# H05R2x_Backend.net
KiCad netlist of a schematic drawn in Altium Designer
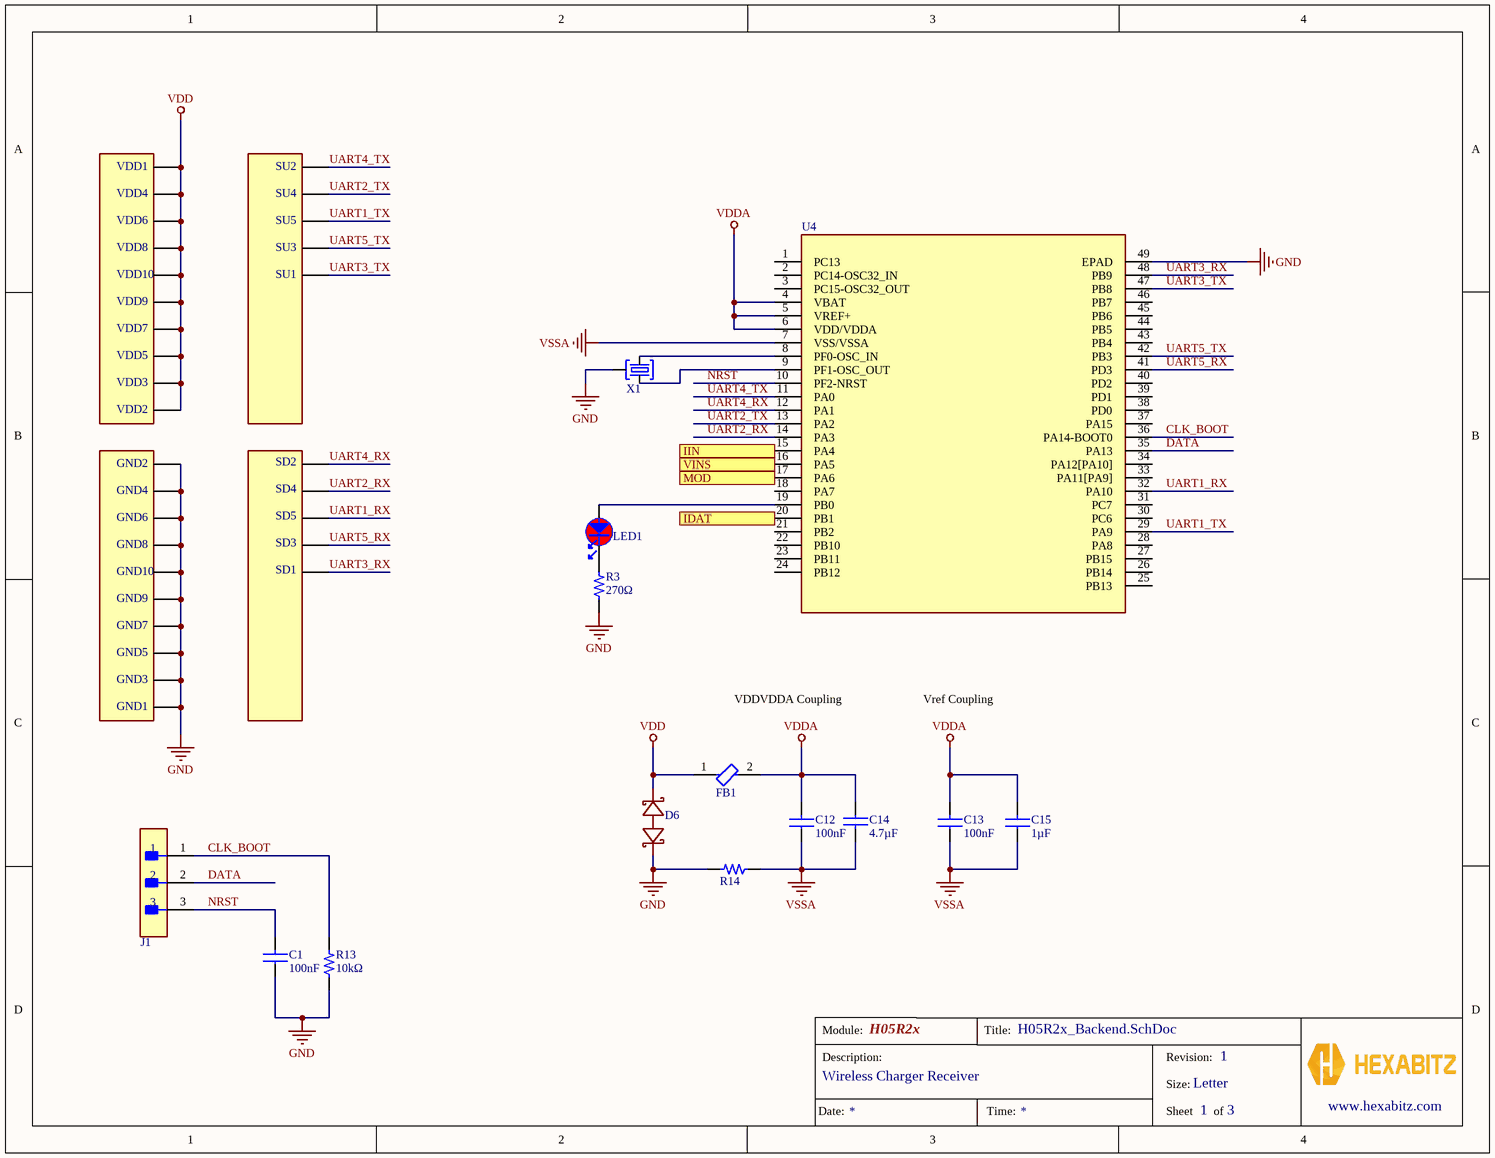
[diagram p0: H05R2x_Backend.SchDoc]

(export (version "E")
  (design (tool "Eeschema 10.0.6"))
  (components
    (comp (ref "C1")
      (value "100nF")
      (footprint "C0603")
      (fields
        (field (name "MANUFACTURER") "Samsung Electro-Mechanics")
        (field (name "MANUFACTURER PART NUMBER") "CL10B104KA8NNNC")
        (field (name "TOLERANCE") "10%")
      )
      (libsource (lib "Hexabitz Altium Library") (part "generic Capacitor"))
    )
    (comp (ref "C12")
      (value "100nF")
      (footprint "C0603")
      (fields
        (field (name "MANUFACTURER") "Samsung Electro-Mechanics")
        (field (name "MANUFACTURER PART NUMBER") "CL10B104KA8NNNC")
        (field (name "TOLERANCE") "10%")
      )
      (libsource (lib "Hexabitz Altium Library") (part "generic Capacitor"))
    )
    (comp (ref "C13")
      (value "100nF")
      (footprint "C0603")
      (fields
        (field (name "MANUFACTURER") "Samsung Electro-Mechanics")
        (field (name "MANUFACTURER PART NUMBER") "CL10B104KA8NNNC")
        (field (name "TOLERANCE") "10%")
      )
      (libsource (lib "Hexabitz Altium Library") (part "generic Capacitor"))
    )
    (comp (ref "C14")
      (value "4.7µF")
      (footprint "C0805")
      (fields
        (field (name "MANUFACTURER") "Samsung Electro-Mechanics")
        (field (name "MANUFACTURER PART NUMBER") "CL21X475KAQNNNE")
        (field (name "TOLERANCE") "10%")
      )
      (libsource (lib "Hexabitz Altium Library") (part "generic Capacitor"))
    )
    (comp (ref "C15")
      (value "1µF")
      (footprint "C0805")
      (description "Ceramic Capacitor, Ceramic, 16V, 10% +Tol, 10% -Tol, X7R, 15% TC, 1uF, Surface Mount, 0805")
      (fields
        (field (name "MANUFACTURER") "Yageo Group")
        (field (name "MANUFACTURER PART NUMBER") "CC0805KKX7R7BB105")
      )
      (libsource (lib "Hexabitz Altium Library") (part "generic Capacitor"))
    )
    (comp (ref "D6")
      (value "CDSOD323-T03SC")
      (footprint "SOD2513X114N")
      (description "A 3V, 350W, bi-directional, standard capacitance, SOD323 pkg TVS Diode ¦ Bourns CDSOD323-T03SC")
      (fields (field (name "MANUFACTURER") "Bourns"))
      (libsource (lib "Hexabitz Altium Library") (part "CDSOD323-T03SC"))
    )
    (comp (ref "FB1")
      (value "MMZ1608Y300B")
      (footprint "FP-MMZ1608-0_8-MFG")
      (description "Ferrite Beads 0603 30ohms 1500mA Signal Line AEC-Q200")
      (fields
        (field (name "MANUFACTURER") "TDK")
        (field (name "MANUFACTURER PART NUMBER") "MMZ1608Y300BTD25")
      )
      (libsource (lib "Hexabitz Altium Library") (part "MMZ1608Y300B"))
    )
    (comp (ref "GND1")
      (value "HEXABIT_UART_PORT")
      (footprint "HEXABIT_POWER_PORT_D")
      (libsource (lib "hexabitz_connectors.Library") (part "HEXABIT_POWER_PORT_D"))
    )
    (comp (ref "GND2")
      (value "HEXABIT_UART_PORT")
      (footprint "HEXABIT_POWER_PORT_D")
      (libsource (lib "hexabitz_connectors.Library") (part "HEXABIT_POWER_PORT_D"))
    )
    (comp (ref "GND3")
      (value "HEXABIT_UART_PORT")
      (footprint "HEXABIT_POWER_PORT_D")
      (libsource (lib "hexabitz_connectors.Library") (part "HEXABIT_POWER_PORT_D"))
    )
    (comp (ref "GND4")
      (value "HEXABIT_UART_PORT")
      (footprint "HEXABIT_POWER_PORT_D")
      (libsource (lib "hexabitz_connectors.Library") (part "HEXABIT_POWER_PORT_D"))
    )
    (comp (ref "GND5")
      (value "HEXABIT_UART_PORT")
      (footprint "HEXABIT_POWER_PORT_D_300L")
      (libsource (lib "hexabitz_connectors.Library") (part "HEXABIT_POWER_PORT_D_300L"))
    )
    (comp (ref "GND6")
      (value "HEXABIT_UART_PORT")
      (footprint "HEXABIT_POWER_PORT_D_300R")
      (libsource (lib "hexabitz_connectors.Library") (part "HEXABIT_POWER_PORT_D_300R"))
    )
    (comp (ref "GND7")
      (value "HEXABIT_UART_PORT")
      (footprint "HEXABIT_POWER_PORT_D")
      (libsource (lib "hexabitz_connectors.Library") (part "HEXABIT_POWER_PORT_D"))
    )
    (comp (ref "GND8")
      (value "HEXABIT_UART_PORT")
      (footprint "HEXABIT_POWER_PORT_D")
      (libsource (lib "hexabitz_connectors.Library") (part "HEXABIT_POWER_PORT_D"))
    )
    (comp (ref "GND9")
      (value "HEXABIT_UART_PORT")
      (footprint "HEXABIT_POWER_PORT_D")
      (libsource (lib "hexabitz_connectors.Library") (part "HEXABIT_POWER_PORT_D"))
    )
    (comp (ref "GND10")
      (value "HEXABIT_UART_PORT")
      (footprint "HEXABIT_POWER_PORT_D")
      (libsource (lib "hexabitz_connectors.Library") (part "HEXABIT_POWER_PORT_D"))
    )
    (comp (ref "J1")
      (value "TSW-103-14-G-S")
      (footprint "FP-TSW-103-14-G-S-MFG")
      (description "CONN HEADER VERT 3POS 2.54MM")
      (libsource (lib "Altium Content Vault") (part "cd3439d6ef35ae5d9b27ec4fdd3e828"))
    )
    (comp (ref "LED1")
      (value "VLMS1300-GS08")
      (footprint "FP-6_541-5092_01-4-MFG")
      (description "LED Uni-Color Super Red 639nm 2-Pin Chip 0603(1608Metric) T/R")
      (fields (field (name "MANUFACTURER") "Vishay Semiconductors"))
      (libsource (lib "Hexabitz Altium Library") (part "VLMS1300-GS08"))
    )
    (comp (ref "R3")
      (value "270Ω")
      (footprint "R0603")
      (description "Res Thick Film 0603 270 Ohm 5% 0.1W(1/10W) ±200ppm/C Pad SMD Automotive T/R")
      (fields
        (field (name "MANUFACTURER") "Panasonic")
        (field (name "MANUFACTURER PART NUMBER") "ERJ-3GEYJ271V")
      )
      (libsource (lib "Hexabitz Altium Library") (part "generic Resistor"))
    )
    (comp (ref "R13")
      (value "10kΩ")
      (footprint "R0603")
      (description "100mW Thick Film Resistors ±100ppm/℃ ±1% 10kΩ 0603 Chip Resistor - Surface Mount ROHS")
      (fields
        (field (name "MANUFACTURER") "Yageo Group")
        (field (name "MANUFACTURER PART NUMBER") "RC0603FR-0710KL")
      )
      (libsource (lib "") (part "generic Resistor_1"))
    )
    (comp (ref "R14")
      (value "Manufacturer Part Number")
      (footprint "R0603")
      (libsource (lib "") (part "generic Resistor_2"))
    )
    (comp (ref "SD1")
      (value "HEXABIT_UART_PORT")
      (footprint "HEXABIT_UART_PORT_D")
      (libsource (lib "hexabitz_connectors.Library") (part "HEXABIT_UART_PORT_D"))
    )
    (comp (ref "SD2")
      (value "HEXABIT_UART_PORT")
      (footprint "HEXABIT_UART_PORT_D")
      (libsource (lib "hexabitz_connectors.Library") (part "HEXABIT_UART_PORT_D"))
    )
    (comp (ref "SD3")
      (value "HEXABIT_UART_PORT")
      (footprint "HEXABIT_UART_PORT_D")
      (libsource (lib "hexabitz_connectors.Library") (part "HEXABIT_UART_PORT_D"))
    )
    (comp (ref "SD4")
      (value "HEXABIT_UART_PORT")
      (footprint "HEXABIT_UART_PORT_D")
      (libsource (lib "hexabitz_connectors.Library") (part "HEXABIT_UART_PORT_D"))
    )
    (comp (ref "SD5")
      (value "HEXABIT_UART_PORT")
      (footprint "HEXABIT_UART_PORT_D")
      (libsource (lib "hexabitz_connectors.Library") (part "HEXABIT_UART_PORT_D"))
    )
    (comp (ref "SU1")
      (value "HEXABIT_UART_PORT")
      (footprint "HEXABIT_UART_PORT_U")
      (libsource (lib "hexabitz_connectors.Library") (part "HEXABIT_UART_PORT_U"))
    )
    (comp (ref "SU2")
      (value "HEXABIT_UART_PORT")
      (footprint "HEXABIT_UART_PORT_U")
      (libsource (lib "hexabitz_connectors.Library") (part "HEXABIT_UART_PORT_U"))
    )
    (comp (ref "SU3")
      (value "HEXABIT_UART_PORT")
      (footprint "HEXABIT_UART_PORT_U")
      (libsource (lib "hexabitz_connectors.Library") (part "HEXABIT_UART_PORT_U"))
    )
    (comp (ref "SU4")
      (value "HEXABIT_UART_PORT")
      (footprint "HEXABIT_UART_PORT_U")
      (libsource (lib "hexabitz_connectors.Library") (part "HEXABIT_UART_PORT_U"))
    )
    (comp (ref "SU5")
      (value "HEXABIT_UART_PORT")
      (footprint "HEXABIT_UART_PORT_U")
      (libsource (lib "hexabitz_connectors.Library") (part "HEXABIT_UART_PORT_U"))
    )
    (comp (ref "U4")
      (value "STM32G0B1CEU6")
      (footprint "QFN50P700X700X65-49N-D")
      (description "MCU 32-bit ARM Cortex M0+ RISC 512KB Flash 1.8V/2.5V/3.3V 48-Pin UFQFPN EP Tray")
      (fields (field (name "MANUFACTURER") "STMicroelectronics"))
      (libsource (lib "Hexabitz Altium Library") (part "STM32G0B1CEU6"))
    )
    (comp (ref "VDD1")
      (value "HEXABIT_UART_PORT")
      (footprint "HEXABIT_POWER_PORT_U")
      (libsource (lib "hexabitz_connectors.Library") (part "HEXABIT_POWER_PORT_U"))
    )
    (comp (ref "VDD2")
      (value "HEXABIT_UART_PORT")
      (footprint "HEXABIT_POWER_PORT_U")
      (libsource (lib "hexabitz_connectors.Library") (part "HEXABIT_POWER_PORT_U"))
    )
    (comp (ref "VDD3")
      (value "HEXABIT_UART_PORT")
      (footprint "HEXABIT_POWER_PORT_U")
      (libsource (lib "hexabitz_connectors.Library") (part "HEXABIT_POWER_PORT_U"))
    )
    (comp (ref "VDD4")
      (value "HEXABIT_UART_PORT")
      (footprint "HEXABIT_POWER_PORT_U")
      (libsource (lib "hexabitz_connectors.Library") (part "HEXABIT_POWER_PORT_U"))
    )
    (comp (ref "VDD5")
      (value "HEXABIT_UART_PORT")
      (footprint "HEXABIT_POWER_PORT_U_300L")
      (libsource (lib "hexabitz_connectors.Library") (part "HEXABIT_POWER_PORT_U_300L"))
    )
    (comp (ref "VDD6")
      (value "HEXABIT_UART_PORT")
      (footprint "HEXABIT_POWER_PORT_U_300R")
      (libsource (lib "hexabitz_connectors.Library") (part "HEXABIT_POWER_PORT_U_300R"))
    )
    (comp (ref "VDD7")
      (value "HEXABIT_UART_PORT")
      (footprint "HEXABIT_POWER_PORT_U")
      (libsource (lib "hexabitz_connectors.Library") (part "HEXABIT_POWER_PORT_U"))
    )
    (comp (ref "VDD8")
      (value "HEXABIT_UART_PORT")
      (footprint "HEXABIT_POWER_PORT_U")
      (libsource (lib "hexabitz_connectors.Library") (part "HEXABIT_POWER_PORT_U"))
    )
    (comp (ref "VDD9")
      (value "HEXABIT_UART_PORT")
      (footprint "HEXABIT_POWER_PORT_U")
      (libsource (lib "hexabitz_connectors.Library") (part "HEXABIT_POWER_PORT_U"))
    )
    (comp (ref "VDD10")
      (value "HEXABIT_UART_PORT")
      (footprint "HEXABIT_POWER_PORT_U")
      (libsource (lib "hexabitz_connectors.Library") (part "HEXABIT_POWER_PORT_U"))
    )
    (comp (ref "X1")
      (value "CSTCE8M00G52Z-R0")
      (footprint "XTALL_CSTCE8M00G52")
      (description "Ceramic Resonator 8MHz ±0.5% (Tol) ±0.2% (Stability) 10pF 40Ohm 3-Pin CSMD T/R")
      (fields (field (name "MANUFACTURER") "Murata") (field (name "TOLERANCE") "0.5%"))
      (libsource (lib "Hexabitz Altium Library") (part "CSTCE8M00G52Z-R0"))
    )
  )
  (nets
    (net (code "1") (name "/CLK_BOOT") (class "Default")
      (node (ref "J1") (pin "1") (pinfunction "1_1") (pintype "passive"))
      (node (ref "R13") (pin "1") (pinfunction "1_1") (pintype "passive"))
      (node (ref "U4") (pin "36") (pinfunction "PA14-BOOT0_36") (pintype "passive"))
    )
    (net (code "2") (name "/DATA") (class "Default")
      (node (ref "J1") (pin "2") (pinfunction "2_2") (pintype "passive"))
      (node (ref "U4") (pin "35") (pinfunction "PA13_35") (pintype "passive"))
    )
    (net (code "3") (name "/IDAT") (class "Default")
      (node (ref "U4") (pin "20") (pinfunction "PB1_20") (pintype "passive"))
    )
    (net (code "4") (name "/IIN") (class "Default")
      (node (ref "U4") (pin "15") (pinfunction "PA4_15") (pintype "passive"))
    )
    (net (code "5") (name "/MOD") (class "Default")
      (node (ref "U4") (pin "17") (pinfunction "PA6_17") (pintype "passive"))
    )
    (net (code "6") (name "/NRST") (class "Default")
      (node (ref "C1") (pin "2") (pinfunction "2_2") (pintype "passive"))
      (node (ref "J1") (pin "3") (pinfunction "3_3") (pintype "passive"))
      (node (ref "U4") (pin "10") (pinfunction "PF2-NRST_10") (pintype "passive"))
    )
    (net (code "7") (name "/UART1_RX") (class "Default")
      (node (ref "SD5") (pin "UART_D") (pinfunction "UART_D_UART_D") (pintype "passive"))
      (node (ref "U4") (pin "32") (pinfunction "PA10_32") (pintype "passive"))
    )
    (net (code "8") (name "/UART1_TX") (class "Default")
      (node (ref "SU5") (pin "UART_U") (pinfunction "UART_U_UART_U") (pintype "passive"))
      (node (ref "U4") (pin "29") (pinfunction "PA9_29") (pintype "passive"))
    )
    (net (code "9") (name "/UART2_RX") (class "Default")
      (node (ref "SD4") (pin "UART_D") (pinfunction "UART_D_UART_D") (pintype "passive"))
      (node (ref "U4") (pin "14") (pinfunction "PA3_14") (pintype "passive"))
    )
    (net (code "10") (name "/UART2_TX") (class "Default")
      (node (ref "SU4") (pin "UART_U") (pinfunction "UART_U_UART_U") (pintype "passive"))
      (node (ref "U4") (pin "13") (pinfunction "PA2_13") (pintype "passive"))
    )
    (net (code "11") (name "/UART3_RX") (class "Default")
      (node (ref "SD1") (pin "UART_D") (pinfunction "UART_D_UART_D") (pintype "passive"))
      (node (ref "U4") (pin "48") (pinfunction "PB9_48") (pintype "passive"))
    )
    (net (code "12") (name "/UART3_TX") (class "Default")
      (node (ref "SU1") (pin "UART_U") (pinfunction "UART_U_UART_U") (pintype "passive"))
      (node (ref "U4") (pin "47") (pinfunction "PB8_47") (pintype "passive"))
    )
    (net (code "13") (name "/UART4_RX") (class "Default")
      (node (ref "SD2") (pin "UART_D") (pinfunction "UART_D_UART_D") (pintype "passive"))
      (node (ref "U4") (pin "12") (pinfunction "PA1_12") (pintype "passive"))
    )
    (net (code "14") (name "/UART4_TX") (class "Default")
      (node (ref "SU2") (pin "UART_U") (pinfunction "UART_U_UART_U") (pintype "passive"))
      (node (ref "U4") (pin "11") (pinfunction "PA0_11") (pintype "passive"))
    )
    (net (code "15") (name "/UART5_RX") (class "Default")
      (node (ref "SD3") (pin "UART_D") (pinfunction "UART_D_UART_D") (pintype "passive"))
      (node (ref "U4") (pin "41") (pinfunction "PD3_41") (pintype "passive"))
    )
    (net (code "16") (name "/UART5_TX") (class "Default")
      (node (ref "SU3") (pin "UART_U") (pinfunction "UART_U_UART_U") (pintype "passive"))
      (node (ref "U4") (pin "42") (pinfunction "PB3_42") (pintype "passive"))
    )
    (net (code "17") (name "/VINS") (class "Default")
      (node (ref "U4") (pin "16") (pinfunction "PA5_16") (pintype "passive"))
    )
    (net (code "18") (name "GND") (class "Default")
      (node (ref "C1") (pin "1") (pinfunction "1_1") (pintype "passive"))
      (node (ref "D6") (pin "1") (pinfunction "A_1") (pintype "passive"))
      (node (ref "GND1") (pin "Pwr_D") (pinfunction "Pwr_D_Pwr_D") (pintype "passive"))
      (node (ref "GND10") (pin "Pwr_D") (pinfunction "Pwr_D_Pwr_D") (pintype "passive"))
      (node (ref "GND2") (pin "Pwr_D") (pinfunction "Pwr_D_Pwr_D") (pintype "passive"))
      (node (ref "GND3") (pin "Pwr_D") (pinfunction "Pwr_D_Pwr_D") (pintype "passive"))
      (node (ref "GND4") (pin "Pwr_D") (pinfunction "Pwr_D_Pwr_D") (pintype "passive"))
      (node (ref "GND5") (pin "Pwr_D") (pinfunction "Pwr_D_Pwr_D") (pintype "passive"))
      (node (ref "GND6") (pin "Pwr_D") (pinfunction "Pwr_D_Pwr_D") (pintype "passive"))
      (node (ref "GND7") (pin "Pwr_D") (pinfunction "Pwr_D_Pwr_D") (pintype "passive"))
      (node (ref "GND8") (pin "Pwr_D") (pinfunction "Pwr_D_Pwr_D") (pintype "passive"))
      (node (ref "GND9") (pin "Pwr_D") (pinfunction "Pwr_D_Pwr_D") (pintype "passive"))
      (node (ref "R13") (pin "2") (pinfunction "2_2") (pintype "passive"))
      (node (ref "R14") (pin "1") (pinfunction "1_1") (pintype "passive"))
      (node (ref "R3") (pin "1") (pinfunction "1_1") (pintype "passive"))
      (node (ref "U4") (pin "49") (pinfunction "EPAD_49") (pintype "passive"))
      (node (ref "X1") (pin "P$2") (pinfunction "2_P$2") (pintype "passive"))
    )
    (net (code "19") (name "Net-(LED1-Pad1)") (class "Default")
      (node (ref "LED1") (pin "1") (pintype "passive"))
      (node (ref "R3") (pin "2") (pinfunction "2_2") (pintype "passive"))
    )
    (net (code "20") (name "Net-(U4-PB0)") (class "Default")
      (node (ref "LED1") (pin "2") (pintype "passive"))
      (node (ref "U4") (pin "19") (pinfunction "PB0_19") (pintype "passive"))
    )
    (net (code "21") (name "Net-(U4-PF0-OSC_IN)") (class "Default")
      (node (ref "U4") (pin "8") (pinfunction "PF0-OSC_IN_8") (pintype "passive"))
      (node (ref "X1") (pin "P$3") (pinfunction "3_P$3") (pintype "passive"))
    )
    (net (code "22") (name "Net-(U4-PF1-OSC_OUT)") (class "Default")
      (node (ref "U4") (pin "9") (pinfunction "PF1-OSC_OUT_9") (pintype "passive"))
      (node (ref "X1") (pin "P$1") (pinfunction "1_P$1") (pintype "passive"))
    )
    (net (code "23") (name "VDD") (class "Default")
      (node (ref "D6") (pin "2") (pinfunction "C_2") (pintype "passive"))
      (node (ref "FB1") (pin "1") (pinfunction "1_1") (pintype "passive"))
      (node (ref "VDD1") (pin "Pwr_U") (pinfunction "Pwr_U_Pwr_U") (pintype "passive"))
      (node (ref "VDD10") (pin "Pwr_U") (pinfunction "Pwr_U_Pwr_U") (pintype "passive"))
      (node (ref "VDD2") (pin "Pwr_U") (pinfunction "Pwr_U_Pwr_U") (pintype "passive"))
      (node (ref "VDD3") (pin "Pwr_U") (pinfunction "Pwr_U_Pwr_U") (pintype "passive"))
      (node (ref "VDD4") (pin "Pwr_U") (pinfunction "Pwr_U_Pwr_U") (pintype "passive"))
      (node (ref "VDD5") (pin "Pwr_U") (pinfunction "Pwr_U_Pwr_U") (pintype "passive"))
      (node (ref "VDD6") (pin "Pwr_U") (pinfunction "Pwr_U_Pwr_U") (pintype "passive"))
      (node (ref "VDD7") (pin "Pwr_U") (pinfunction "Pwr_U_Pwr_U") (pintype "passive"))
      (node (ref "VDD8") (pin "Pwr_U") (pinfunction "Pwr_U_Pwr_U") (pintype "passive"))
      (node (ref "VDD9") (pin "Pwr_U") (pinfunction "Pwr_U_Pwr_U") (pintype "passive"))
    )
    (net (code "24") (name "VDDA") (class "Default")
      (node (ref "C12") (pin "2") (pinfunction "2_2") (pintype "passive"))
      (node (ref "C13") (pin "2") (pinfunction "2_2") (pintype "passive"))
      (node (ref "C14") (pin "1") (pinfunction "1_1") (pintype "passive"))
      (node (ref "C15") (pin "2") (pinfunction "2_2") (pintype "passive"))
      (node (ref "FB1") (pin "2") (pinfunction "2_2") (pintype "passive"))
      (node (ref "U4") (pin "4") (pinfunction "VBAT_4") (pintype "passive"))
      (node (ref "U4") (pin "5") (pinfunction "VREF+_5") (pintype "passive"))
      (node (ref "U4") (pin "6") (pinfunction "VDD/VDDA_6") (pintype "passive"))
    )
    (net (code "25") (name "VSSA") (class "Default")
      (node (ref "C12") (pin "1") (pinfunction "1_1") (pintype "passive"))
      (node (ref "C13") (pin "1") (pinfunction "1_1") (pintype "passive"))
      (node (ref "C14") (pin "2") (pinfunction "2_2") (pintype "passive"))
      (node (ref "C15") (pin "1") (pinfunction "1_1") (pintype "passive"))
      (node (ref "R14") (pin "2") (pinfunction "2_2") (pintype "passive"))
      (node (ref "U4") (pin "7") (pinfunction "VSS/VSSA_7") (pintype "passive"))
    )
    (net (code "26") (name "unconnected-(U4-PA7-Pad18)") (class "Default")
      (node (ref "U4") (pin "18") (pinfunction "PA7_18") (pintype "passive"))
    )
    (net (code "27") (name "unconnected-(U4-PA8-Pad28)") (class "Default")
      (node (ref "U4") (pin "28") (pinfunction "PA8_28") (pintype "passive"))
    )
    (net (code "28") (name "unconnected-(U4-PA11[PA9]-Pad33)") (class "Default")
      (node (ref "U4") (pin "33") (pinfunction "PA11[PA9]_33") (pintype "passive"))
    )
    (net (code "29") (name "unconnected-(U4-PA12[PA10]-Pad34)") (class "Default")
      (node (ref "U4") (pin "34") (pinfunction "PA12[PA10]_34") (pintype "passive"))
    )
    (net (code "30") (name "unconnected-(U4-PA15-Pad37)") (class "Default")
      (node (ref "U4") (pin "37") (pinfunction "PA15_37") (pintype "passive"))
    )
    (net (code "31") (name "unconnected-(U4-PB2-Pad21)") (class "Default")
      (node (ref "U4") (pin "21") (pinfunction "PB2_21") (pintype "passive"))
    )
    (net (code "32") (name "unconnected-(U4-PB4-Pad43)") (class "Default")
      (node (ref "U4") (pin "43") (pinfunction "PB4_43") (pintype "passive"))
    )
    (net (code "33") (name "unconnected-(U4-PB5-Pad44)") (class "Default")
      (node (ref "U4") (pin "44") (pinfunction "PB5_44") (pintype "passive"))
    )
    (net (code "34") (name "unconnected-(U4-PB6-Pad45)") (class "Default")
      (node (ref "U4") (pin "45") (pinfunction "PB6_45") (pintype "passive"))
    )
    (net (code "35") (name "unconnected-(U4-PB7-Pad46)") (class "Default")
      (node (ref "U4") (pin "46") (pinfunction "PB7_46") (pintype "passive"))
    )
    (net (code "36") (name "unconnected-(U4-PB10-Pad22)") (class "Default")
      (node (ref "U4") (pin "22") (pinfunction "PB10_22") (pintype "passive"))
    )
    (net (code "37") (name "unconnected-(U4-PB11-Pad23)") (class "Default")
      (node (ref "U4") (pin "23") (pinfunction "PB11_23") (pintype "passive"))
    )
    (net (code "38") (name "unconnected-(U4-PB12-Pad24)") (class "Default")
      (node (ref "U4") (pin "24") (pinfunction "PB12_24") (pintype "passive"))
    )
    (net (code "39") (name "unconnected-(U4-PB13-Pad25)") (class "Default")
      (node (ref "U4") (pin "25") (pinfunction "PB13_25") (pintype "passive"))
    )
    (net (code "40") (name "unconnected-(U4-PB14-Pad26)") (class "Default")
      (node (ref "U4") (pin "26") (pinfunction "PB14_26") (pintype "passive"))
    )
    (net (code "41") (name "unconnected-(U4-PB15-Pad27)") (class "Default")
      (node (ref "U4") (pin "27") (pinfunction "PB15_27") (pintype "passive"))
    )
    (net (code "42") (name "unconnected-(U4-PC6-Pad30)") (class "Default")
      (node (ref "U4") (pin "30") (pinfunction "PC6_30") (pintype "passive"))
    )
    (net (code "43") (name "unconnected-(U4-PC7-Pad31)") (class "Default")
      (node (ref "U4") (pin "31") (pinfunction "PC7_31") (pintype "passive"))
    )
    (net (code "44") (name "unconnected-(U4-PC13-Pad1)") (class "Default")
      (node (ref "U4") (pin "1") (pinfunction "PC13_1") (pintype "passive"))
    )
    (net (code "45") (name "unconnected-(U4-PC14-OSC32_IN-Pad2)") (class "Default")
      (node (ref "U4") (pin "2") (pinfunction "PC14-OSC32_IN_2") (pintype "passive"))
    )
    (net (code "46") (name "unconnected-(U4-PC15-OSC32_OUT-Pad3)") (class "Default")
      (node (ref "U4") (pin "3") (pinfunction "PC15-OSC32_OUT_3") (pintype "passive"))
    )
    (net (code "47") (name "unconnected-(U4-PD0-Pad38)") (class "Default")
      (node (ref "U4") (pin "38") (pinfunction "PD0_38") (pintype "passive"))
    )
    (net (code "48") (name "unconnected-(U4-PD1-Pad39)") (class "Default")
      (node (ref "U4") (pin "39") (pinfunction "PD1_39") (pintype "passive"))
    )
    (net (code "49") (name "unconnected-(U4-PD2-Pad40)") (class "Default")
      (node (ref "U4") (pin "40") (pinfunction "PD2_40") (pintype "passive"))
    )
  )
)
